# 5v-low-power.net
KiCad netlist of a schematic drawn in EAGLE
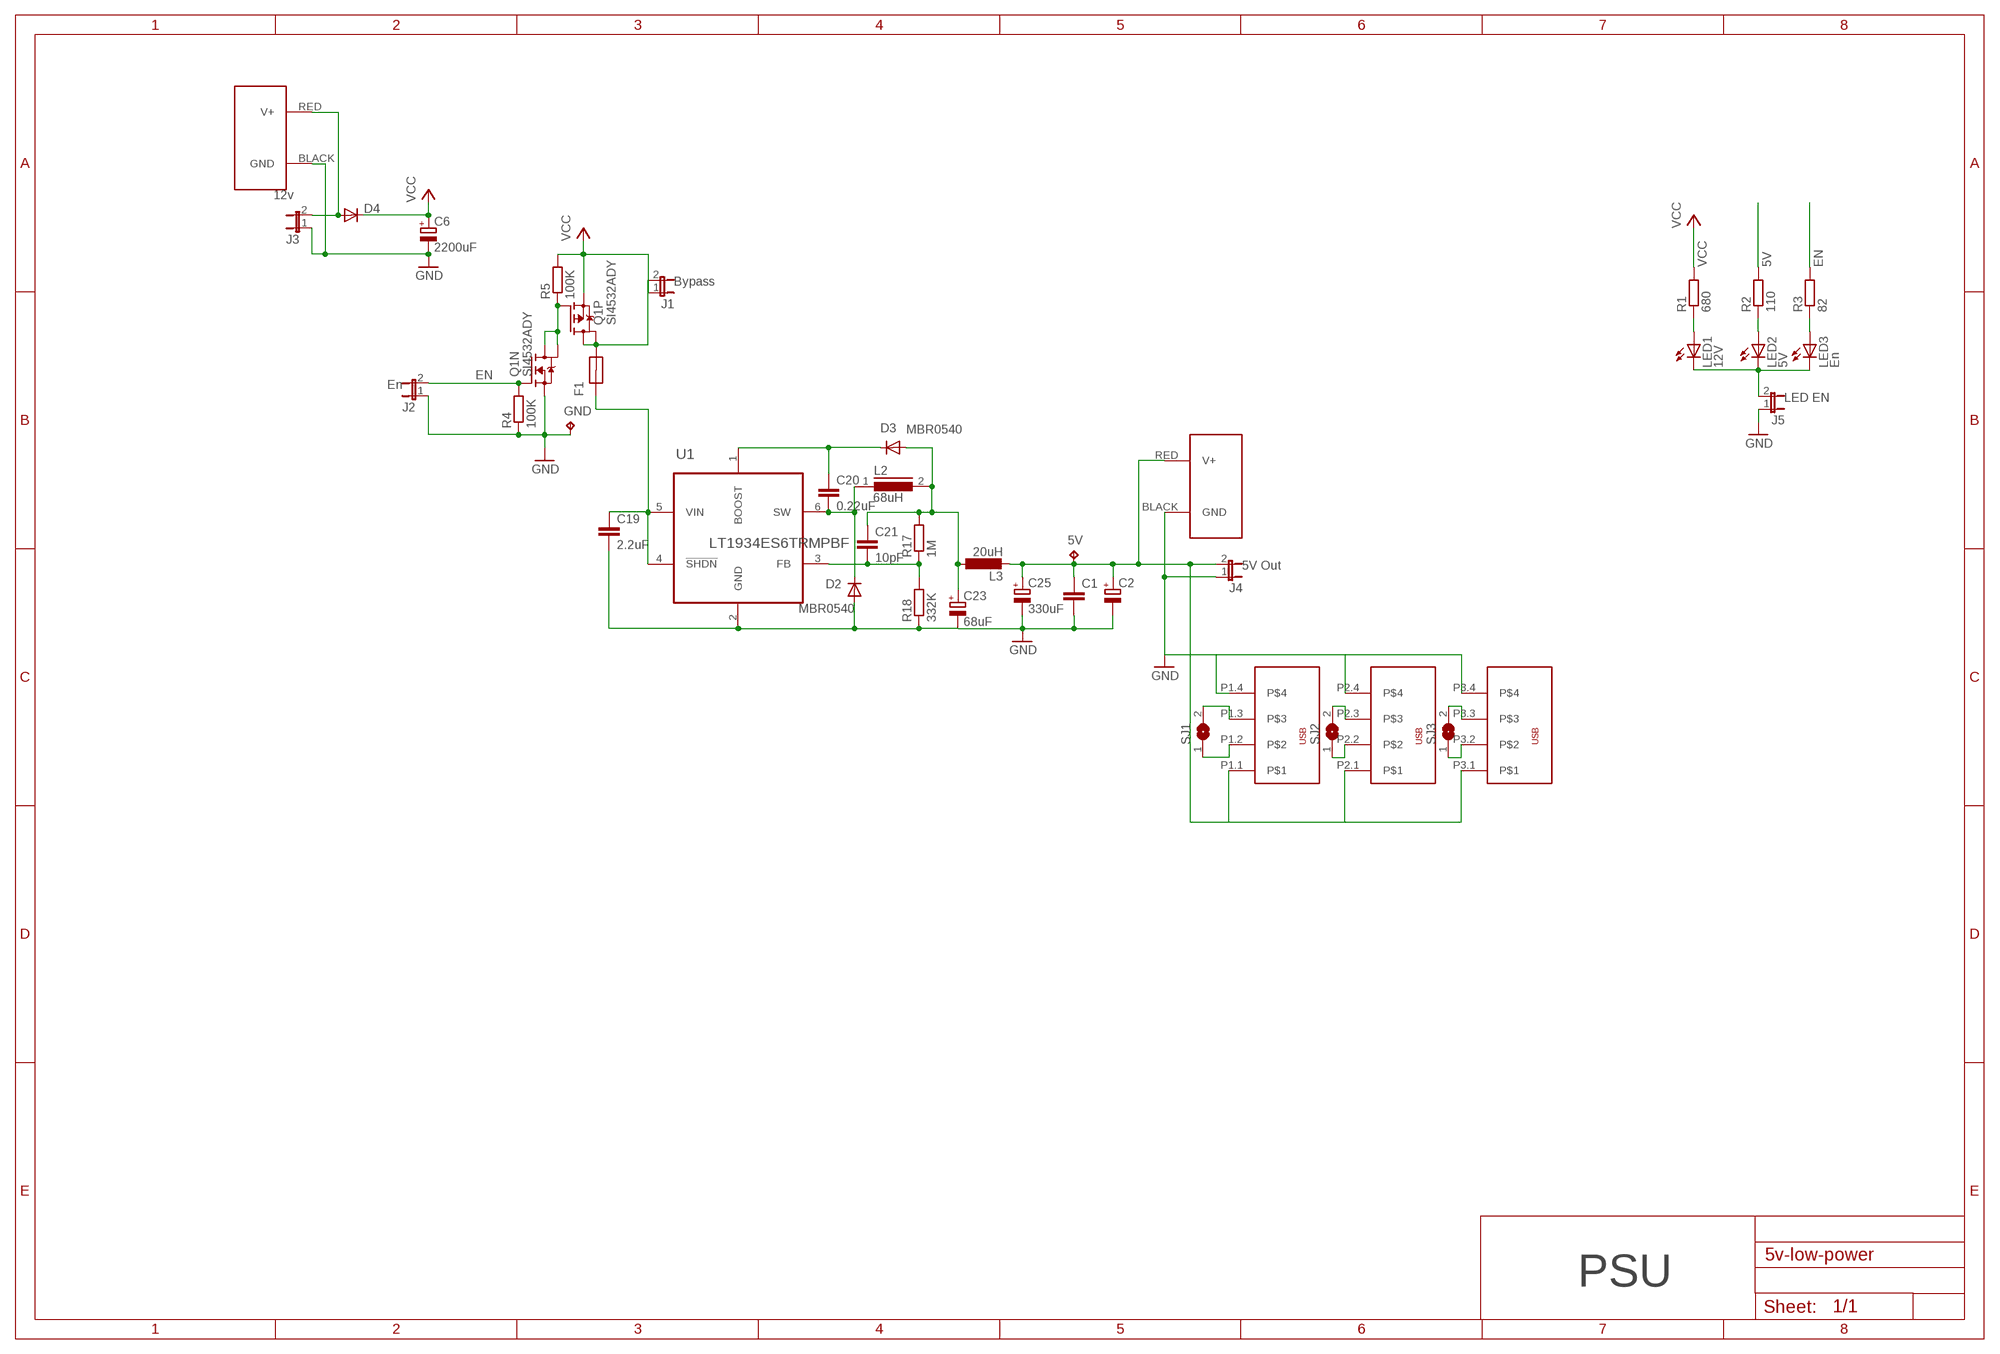
[diagram p0: schematic, sheet 1]

(export (version "E")
  (design (tool "Eeschema 10.0.6"))
  (components
    (comp (ref "5V")
      (value "5V B")
      (footprint "eagle-import:B1,27")
      (libsource (lib "eagle-import") (part "TPB1,27"))
    )
    (comp (ref "C1")
      (value "C-EUC0805")
      (footprint "eagle-import:C0805")
      (libsource (lib "eagle-import") (part "C-EUC0805"))
    )
    (comp (ref "C2")
      (value "CPOL-EUB/3528-21R")
      (footprint "eagle-import:B_3528-21R")
      (libsource (lib "eagle-import") (part "resistor_CPOL-EUB/3528-21R"))
    )
    (comp (ref "C6")
      (value "2200uF")
      (footprint "eagle-import:E5-13")
      (libsource (lib "eagle-import") (part "CPOL-EUE5-13"))
    )
    (comp (ref "C19")
      (value "2.2uF")
      (footprint "eagle-import:C0805")
      (libsource (lib "eagle-import") (part "C-EUC0805"))
    )
    (comp (ref "C20")
      (value "0.22uF")
      (footprint "eagle-import:C0805")
      (libsource (lib "eagle-import") (part "C-EUC0805"))
    )
    (comp (ref "C21")
      (value "10pF")
      (footprint "eagle-import:C0805")
      (libsource (lib "eagle-import") (part "C-EUC0805"))
    )
    (comp (ref "C23")
      (value "68uF")
      (footprint "eagle-import:PANASONIC_E")
      (libsource (lib "eagle-import") (part "CPOL-EUE"))
    )
    (comp (ref "C25")
      (value "330uF")
      (footprint "eagle-import:E5-8,5")
      (libsource (lib "eagle-import") (part "CPOL-EUE5-8.5"))
    )
    (comp (ref "D2")
      (value "MBR0540")
      (footprint "eagle-import:SOD123")
      (libsource (lib "eagle-import") (part "MBR0520LT"))
    )
    (comp (ref "D3")
      (value "MBR0540")
      (footprint "eagle-import:SOD123")
      (libsource (lib "eagle-import") (part "MBR0520LT"))
    )
    (comp (ref "D4")
      (value "DIODE-SMB")
      (footprint "eagle-import:SMB")
      (libsource (lib "eagle-import") (part "DIODE-SMB"))
    )
    (comp (ref "F1")
      (value "MF-MSMF110")
      (footprint "eagle-import:1812")
      (libsource (lib "eagle-import") (part "MF-MSMF110"))
    )
    (comp (ref "GND")
      (value "5V B")
      (footprint "eagle-import:B1,27")
      (libsource (lib "eagle-import") (part "TPB1,27"))
    )
    (comp (ref "J1")
      (value "Bypass")
      (footprint "eagle-import:2-MOLEX")
      (libsource (lib "eagle-import") (part "2-PIN-MOLEX"))
    )
    (comp (ref "J2")
      (value "En")
      (footprint "eagle-import:2-MOLEX")
      (libsource (lib "eagle-import") (part "2-PIN-MOLEX"))
    )
    (comp (ref "J3")
      (value "12v")
      (footprint "eagle-import:2-MOLEX")
      (libsource (lib "eagle-import") (part "2-PIN-MOLEX"))
    )
    (comp (ref "J4")
      (value "5V Out")
      (footprint "eagle-import:2-MOLEX")
      (libsource (lib "eagle-import") (part "2-PIN-MOLEX"))
    )
    (comp (ref "J5")
      (value "LED EN")
      (footprint "eagle-import:2-MOLEX")
      (libsource (lib "eagle-import") (part "2-PIN-MOLEX"))
    )
    (comp (ref "J6")
      (value "POWERPOLE_POWER25A")
      (footprint "eagle-import:POWERPOLE_PAIR_25A")
      (libsource (lib "eagle-import") (part "POWERPOLE_POWER25A"))
    )
    (comp (ref "J7")
      (value "POWERPOLE_POWER25A")
      (footprint "eagle-import:POWERPOLE_PAIR_25A")
      (libsource (lib "eagle-import") (part "POWERPOLE_POWER25A"))
    )
    (comp (ref "L2")
      (value "68uH")
      (footprint "eagle-import:DR127")
      (libsource (lib "eagle-import") (part "DR127"))
    )
    (comp (ref "L3")
      (value "20uH")
      (footprint "eagle-import:6000-XXXX-RC")
      (libsource (lib "eagle-import") (part "L-EU6000-XXX-RC"))
    )
    (comp (ref "LED1")
      (value "12V")
      (footprint "eagle-import:CHIP-LED0805")
      (libsource (lib "eagle-import") (part "LEDCHIP-LED0805"))
    )
    (comp (ref "LED2")
      (value "5V")
      (footprint "eagle-import:CHIP-LED0805")
      (libsource (lib "eagle-import") (part "LEDCHIP-LED0805"))
    )
    (comp (ref "LED3")
      (value "En")
      (footprint "eagle-import:CHIP-LED0805")
      (libsource (lib "eagle-import") (part "LEDCHIP-LED0805"))
    )
    (comp (ref "Q1")
      (value "SI4532ADY")
      (footprint "eagle-import:SO8")
      (libsource (lib "eagle-import") (part "SI4532ADY"))
    )
    (comp (ref "R1")
      (value "680")
      (footprint "eagle-import:R0805")
      (libsource (lib "eagle-import") (part "R-EU_R0805"))
    )
    (comp (ref "R2")
      (value "110")
      (footprint "eagle-import:R0805")
      (libsource (lib "eagle-import") (part "R-EU_R0805"))
    )
    (comp (ref "R3")
      (value "82")
      (footprint "eagle-import:R0805")
      (libsource (lib "eagle-import") (part "R-EU_R0805"))
    )
    (comp (ref "R4")
      (value "100K")
      (footprint "eagle-import:R0805")
      (libsource (lib "eagle-import") (part "R-EU_R0805"))
    )
    (comp (ref "R5")
      (value "100K")
      (footprint "eagle-import:R0805")
      (libsource (lib "eagle-import") (part "R-EU_R0805"))
    )
    (comp (ref "R17")
      (value "1M")
      (footprint "eagle-import:R0805")
      (libsource (lib "eagle-import") (part "R-EU_R0805"))
    )
    (comp (ref "R18")
      (value "332K")
      (footprint "eagle-import:R0805")
      (libsource (lib "eagle-import") (part "R-EU_R0805"))
    )
    (comp (ref "SJ1") (value "SJ") (footprint "eagle-import:SJ") (libsource (lib "eagle-import") (part "SJ")))
    (comp (ref "SJ2") (value "SJ") (footprint "eagle-import:SJ") (libsource (lib "eagle-import") (part "SJ")))
    (comp (ref "SJ3") (value "SJ") (footprint "eagle-import:SJ") (libsource (lib "eagle-import") (part "SJ")))
    (comp (ref "U$1")
      (value "USB_DUAL_VERT+HORIZTRIPPLE")
      (footprint "eagle-import:USB_DUAL_HORIZ+VERT")
      (libsource (lib "eagle-import") (part "USB_DUAL_VERT+HORIZTRIPPLE"))
    )
    (comp (ref "U1")
      (value "LT1934ES6TRMPBF")
      (footprint "eagle-import:SOT95P280X100-6N")
      (fields (field (name "MPN") "LT1934ES6#TRMPBF"))
      (libsource (lib "eagle-import") (part "LT1934ES6TRMPBF"))
    )
  )
  (nets
    (net (code "1") (name "/5V") (class "Default")
      (node (ref "5V") (pin "TP") (pinfunction "TP_TP") (pintype "input"))
      (node (ref "C1") (pin "1") (pinfunction "1_1") (pintype "passive"))
      (node (ref "C2") (pin "+") (pinfunction "+_+") (pintype "passive"))
      (node (ref "C25") (pin "+") (pinfunction "+_+") (pintype "passive"))
      (node (ref "J4") (pin "2") (pinfunction "2_2") (pintype "passive"))
      (node (ref "J6") (pin "RED") (pinfunction "V+_RED") (pintype "power_in"))
      (node (ref "L3") (pin "2") (pinfunction "2_2") (pintype "passive"))
      (node (ref "R2") (pin "2") (pinfunction "2_2") (pintype "passive"))
      (node (ref "U$1") (pin "P1.1") (pinfunction "P$1_P1.1") (pintype "bidirectional"))
      (node (ref "U$1") (pin "P2.1") (pinfunction "P$1_P2.1") (pintype "bidirectional"))
      (node (ref "U$1") (pin "P3.1") (pinfunction "P$1_P3.1") (pintype "bidirectional"))
    )
    (net (code "2") (name "/EN") (class "Default")
      (node (ref "J2") (pin "2") (pinfunction "2_2") (pintype "passive"))
      (node (ref "Q1") (pin "2") (pinfunction "G_2") (pintype "passive"))
      (node (ref "R3") (pin "2") (pinfunction "2_2") (pintype "passive"))
      (node (ref "R4") (pin "2") (pinfunction "2_2") (pintype "passive"))
    )
    (net (code "3") (name "GND") (class "Default")
      (node (ref "C1") (pin "2") (pinfunction "2_2") (pintype "passive"))
      (node (ref "C19") (pin "2") (pinfunction "2_2") (pintype "passive"))
      (node (ref "C2") (pin "-") (pinfunction "-_-") (pintype "passive"))
      (node (ref "C23") (pin "-") (pinfunction "-_-") (pintype "passive"))
      (node (ref "C25") (pin "-") (pinfunction "-_-") (pintype "passive"))
      (node (ref "C6") (pin "-") (pinfunction "-_-") (pintype "passive"))
      (node (ref "D2") (pin "A") (pinfunction "A_A") (pintype "passive"))
      (node (ref "GND") (pin "TP") (pinfunction "TP_TP") (pintype "input"))
      (node (ref "J2") (pin "1") (pinfunction "1_1") (pintype "passive"))
      (node (ref "J3") (pin "1") (pinfunction "1_1") (pintype "passive"))
      (node (ref "J4") (pin "1") (pinfunction "1_1") (pintype "passive"))
      (node (ref "J5") (pin "1") (pinfunction "1_1") (pintype "passive"))
      (node (ref "J6") (pin "BLACK") (pinfunction "GND_BLACK") (pintype "power_in"))
      (node (ref "J7") (pin "BLACK") (pinfunction "GND_BLACK") (pintype "power_in"))
      (node (ref "Q1") (pin "1") (pinfunction "S_1") (pintype "passive"))
      (node (ref "R18") (pin "1") (pinfunction "1_1") (pintype "passive"))
      (node (ref "R4") (pin "1") (pinfunction "1_1") (pintype "passive"))
      (node (ref "U$1") (pin "P1.4") (pinfunction "P$4_P1.4") (pintype "bidirectional"))
      (node (ref "U$1") (pin "P2.4") (pinfunction "P$4_P2.4") (pintype "bidirectional"))
      (node (ref "U$1") (pin "P3.4") (pinfunction "P$4_P3.4") (pintype "bidirectional"))
      (node (ref "U1") (pin "2") (pinfunction "GND_2") (pintype "passive"))
    )
    (net (code "4") (name "Net-(C21-Pad1)") (class "Default")
      (node (ref "C21") (pin "1") (pinfunction "1_1") (pintype "passive"))
      (node (ref "C23") (pin "+") (pinfunction "+_+") (pintype "passive"))
      (node (ref "D3") (pin "A") (pinfunction "A_A") (pintype "passive"))
      (node (ref "L2") (pin "2") (pinfunction "2_2") (pintype "passive"))
      (node (ref "L3") (pin "1") (pinfunction "1_1") (pintype "passive"))
      (node (ref "R17") (pin "2") (pinfunction "2_2") (pintype "passive"))
    )
    (net (code "5") (name "Net-(F1-P$1)") (class "Default")
      (node (ref "C19") (pin "1") (pinfunction "1_1") (pintype "passive"))
      (node (ref "F1") (pin "1") (pinfunction "P$1_1") (pintype "bidirectional"))
      (node (ref "U1") (pin "4") (pinfunction "~{SHDN}_4") (pintype "input"))
      (node (ref "U1") (pin "5") (pinfunction "VIN_5") (pintype "power_in"))
    )
    (net (code "6") (name "Net-(F1-P$2)") (class "Default")
      (node (ref "F1") (pin "2") (pinfunction "P$2_2") (pintype "bidirectional"))
      (node (ref "J1") (pin "2") (pinfunction "2_2") (pintype "passive"))
      (node (ref "Q1") (pin "5") (pinfunction "D_5") (pintype "passive"))
      (node (ref "Q1") (pin "6") (pinfunction "D_6") (pintype "passive"))
    )
    (net (code "7") (name "Net-(J5-Pad2)") (class "Default")
      (node (ref "J5") (pin "2") (pinfunction "2_2") (pintype "passive"))
      (node (ref "LED1") (pin "C") (pinfunction "C_C") (pintype "passive"))
      (node (ref "LED2") (pin "C") (pinfunction "C_C") (pintype "passive"))
      (node (ref "LED3") (pin "C") (pinfunction "C_C") (pintype "passive"))
    )
    (net (code "8") (name "Net-(J7-V+)") (class "Default")
      (node (ref "D4") (pin "A") (pinfunction "A_A") (pintype "passive"))
      (node (ref "J3") (pin "2") (pinfunction "2_2") (pintype "passive"))
      (node (ref "J7") (pin "RED") (pinfunction "V+_RED") (pintype "power_in"))
    )
    (net (code "9") (name "Net-(LED1-PadA)") (class "Default")
      (node (ref "LED1") (pin "A") (pinfunction "A_A") (pintype "passive"))
      (node (ref "R1") (pin "1") (pinfunction "1_1") (pintype "passive"))
    )
    (net (code "10") (name "Net-(LED2-PadA)") (class "Default")
      (node (ref "LED2") (pin "A") (pinfunction "A_A") (pintype "passive"))
      (node (ref "R2") (pin "1") (pinfunction "1_1") (pintype "passive"))
    )
    (net (code "11") (name "Net-(LED3-PadA)") (class "Default")
      (node (ref "LED3") (pin "A") (pinfunction "A_A") (pintype "passive"))
      (node (ref "R3") (pin "1") (pinfunction "1_1") (pintype "passive"))
    )
    (net (code "12") (name "Net-(Q1B-G)") (class "Default")
      (node (ref "Q1") (pin "4") (pinfunction "G_4") (pintype "passive"))
      (node (ref "Q1") (pin "7") (pinfunction "D_7") (pintype "passive"))
      (node (ref "Q1") (pin "8") (pinfunction "D_8") (pintype "passive"))
      (node (ref "R5") (pin "1") (pinfunction "1_1") (pintype "passive"))
    )
    (net (code "13") (name "Net-(U$1A-P$2)") (class "Default")
      (node (ref "SJ1") (pin "1") (pinfunction "1_1") (pintype "passive"))
      (node (ref "U$1") (pin "P1.2") (pinfunction "P$2_P1.2") (pintype "bidirectional"))
    )
    (net (code "14") (name "Net-(U$1A-P$3)") (class "Default")
      (node (ref "SJ1") (pin "2") (pinfunction "2_2") (pintype "passive"))
      (node (ref "U$1") (pin "P1.3") (pinfunction "P$3_P1.3") (pintype "bidirectional"))
    )
    (net (code "15") (name "Net-(U$1B-P$2)") (class "Default")
      (node (ref "SJ2") (pin "1") (pinfunction "1_1") (pintype "passive"))
      (node (ref "U$1") (pin "P2.2") (pinfunction "P$2_P2.2") (pintype "bidirectional"))
    )
    (net (code "16") (name "Net-(U$1B-P$3)") (class "Default")
      (node (ref "SJ2") (pin "2") (pinfunction "2_2") (pintype "passive"))
      (node (ref "U$1") (pin "P2.3") (pinfunction "P$3_P2.3") (pintype "bidirectional"))
    )
    (net (code "17") (name "Net-(U$1C-P$2)") (class "Default")
      (node (ref "SJ3") (pin "1") (pinfunction "1_1") (pintype "passive"))
      (node (ref "U$1") (pin "P3.2") (pinfunction "P$2_P3.2") (pintype "bidirectional"))
    )
    (net (code "18") (name "Net-(U$1C-P$3)") (class "Default")
      (node (ref "SJ3") (pin "2") (pinfunction "2_2") (pintype "passive"))
      (node (ref "U$1") (pin "P3.3") (pinfunction "P$3_P3.3") (pintype "bidirectional"))
    )
    (net (code "19") (name "Net-(U1-BOOST)") (class "Default")
      (node (ref "C20") (pin "1") (pinfunction "1_1") (pintype "passive"))
      (node (ref "D3") (pin "C") (pinfunction "C_C") (pintype "passive"))
      (node (ref "U1") (pin "1") (pinfunction "BOOST_1") (pintype "power_in"))
    )
    (net (code "20") (name "Net-(U1-FB)") (class "Default")
      (node (ref "C21") (pin "2") (pinfunction "2_2") (pintype "passive"))
      (node (ref "R17") (pin "1") (pinfunction "1_1") (pintype "passive"))
      (node (ref "R18") (pin "2") (pinfunction "2_2") (pintype "passive"))
      (node (ref "U1") (pin "3") (pinfunction "FB_3") (pintype "input"))
    )
    (net (code "21") (name "Net-(U1-SW)") (class "Default")
      (node (ref "C20") (pin "2") (pinfunction "2_2") (pintype "passive"))
      (node (ref "D2") (pin "C") (pinfunction "C_C") (pintype "passive"))
      (node (ref "L2") (pin "1") (pinfunction "1_1") (pintype "passive"))
      (node (ref "U1") (pin "6") (pinfunction "SW_6") (pintype "output"))
    )
    (net (code "22") (name "VCC") (class "Default")
      (node (ref "C6") (pin "+") (pinfunction "+_+") (pintype "passive"))
      (node (ref "D4") (pin "C") (pinfunction "C_C") (pintype "passive"))
      (node (ref "J1") (pin "1") (pinfunction "1_1") (pintype "passive"))
      (node (ref "Q1") (pin "3") (pinfunction "S_3") (pintype "passive"))
      (node (ref "R1") (pin "2") (pinfunction "2_2") (pintype "passive"))
      (node (ref "R5") (pin "2") (pinfunction "2_2") (pintype "passive"))
    )
  )
)
